# MotionBoard.net
KiCad netlist of a schematic drawn in Altium Designer
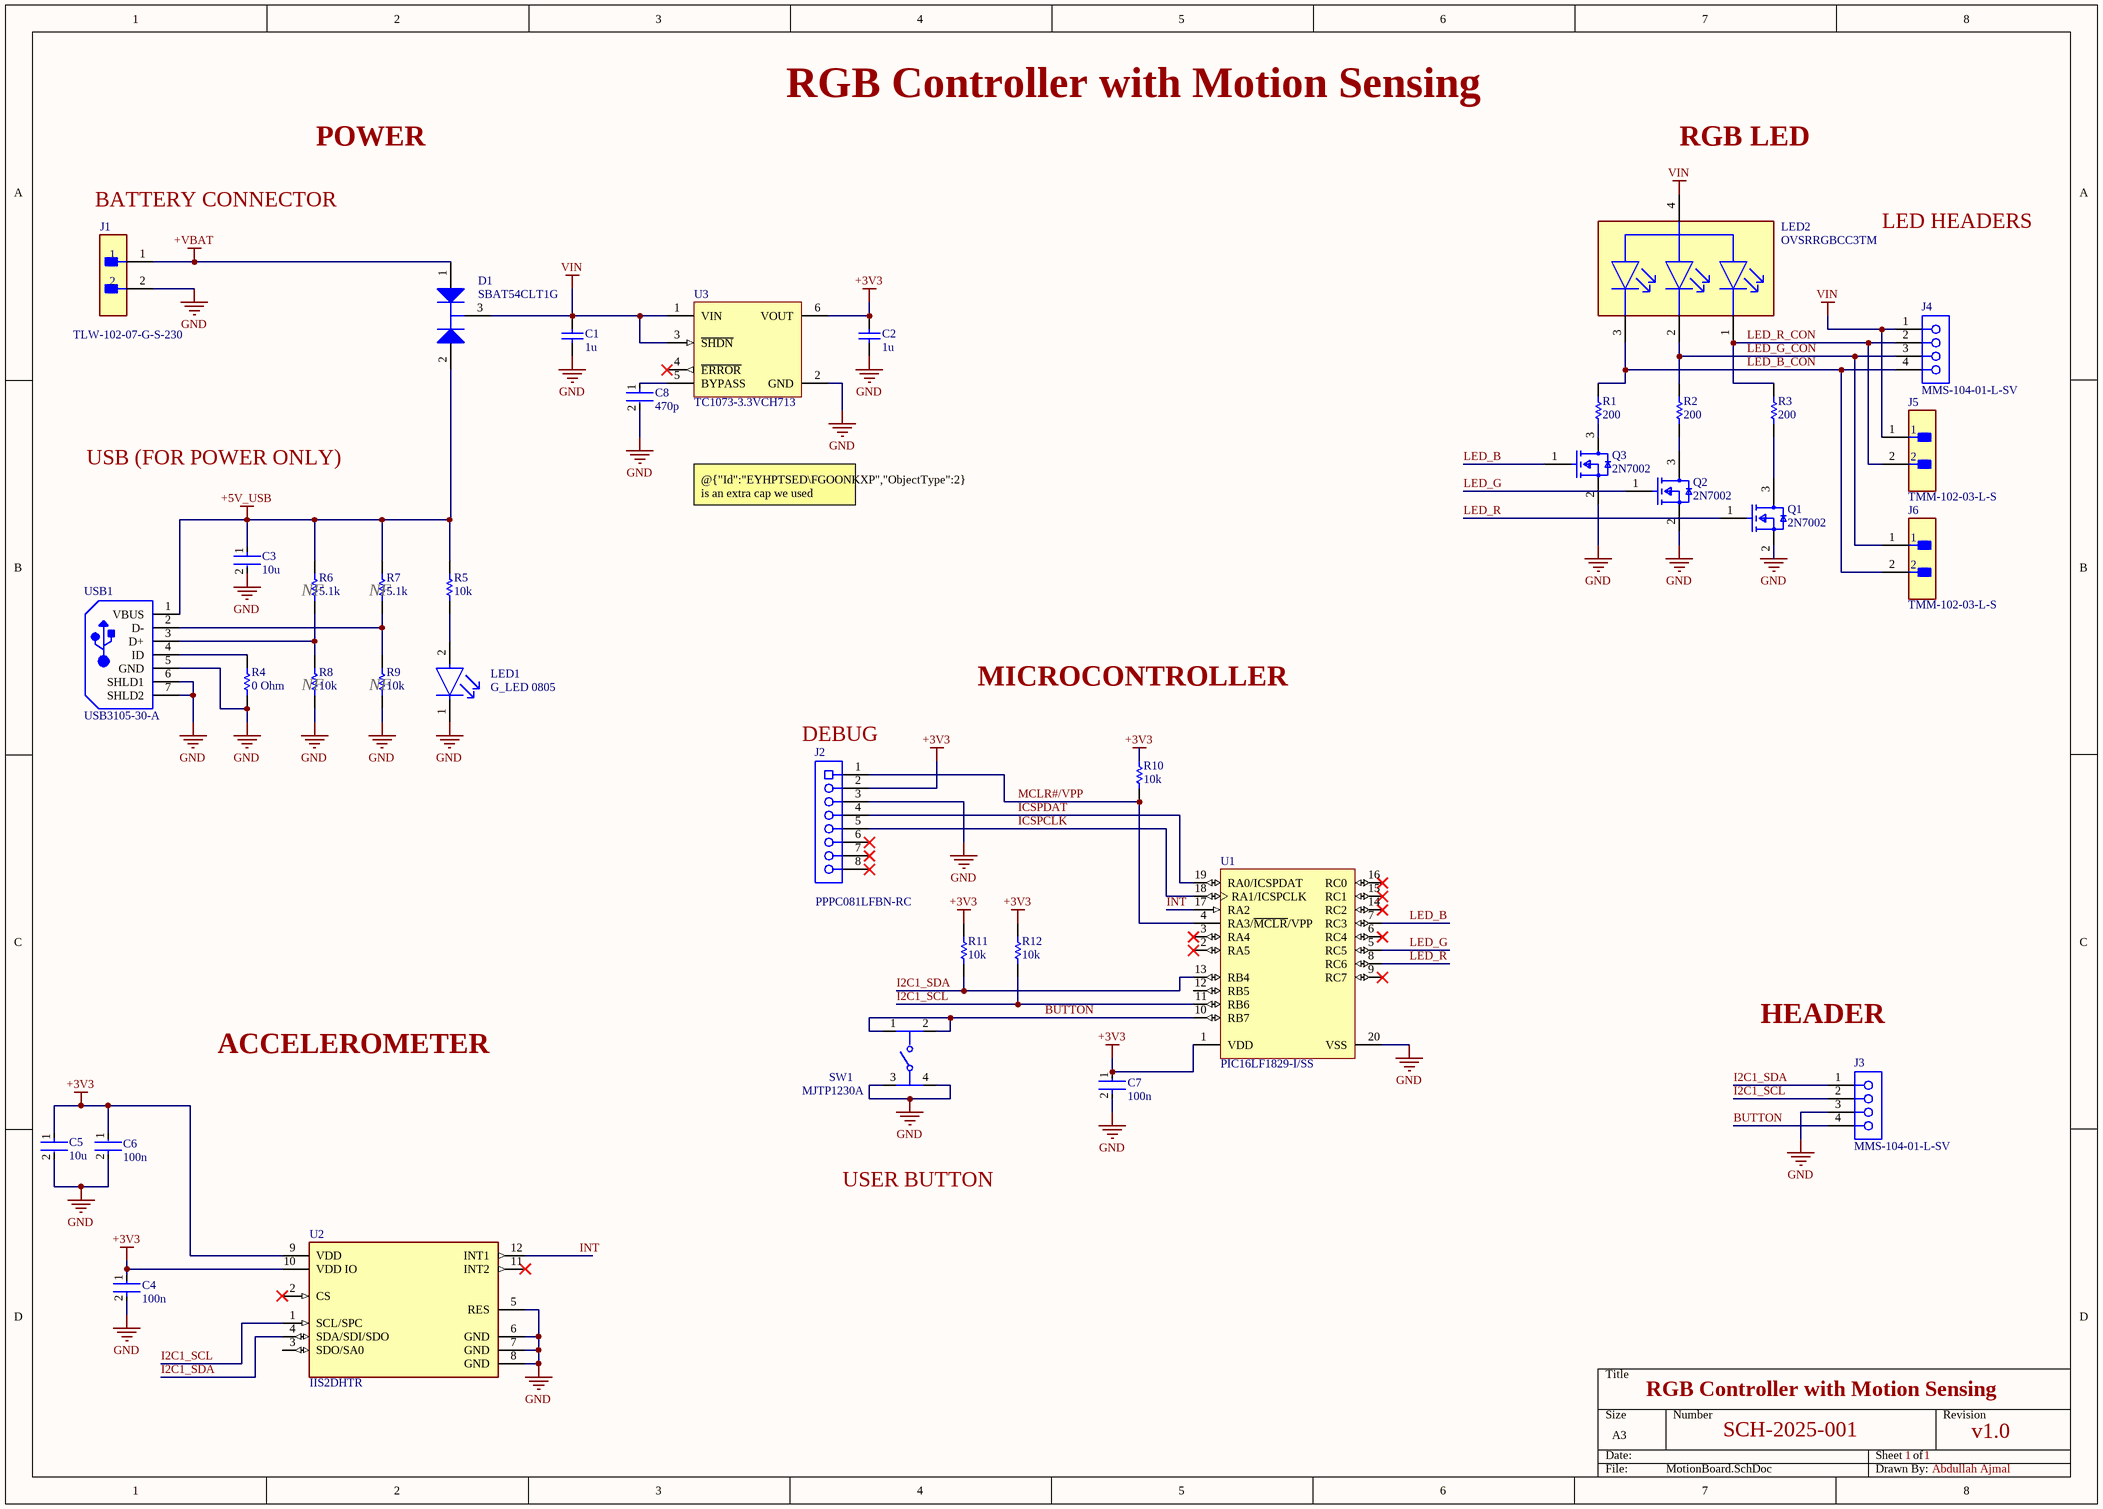
[diagram p0: MotionBoard.SchDoc]

(export (version "E")
  (design (tool "Eeschema 10.0.6"))
  (components
    (comp (ref "C1")
      (value "1u")
      (footprint "CAPC2013X140X50NL20T25")
      (fields (field (name "PART NUMBER") "C0805C105M4PACTU") (field (name "MANUFACTURER") "Kemet"))
      (libsource (lib "Altium Content Vault") (part "CAP"))
    )
    (comp (ref "C2")
      (value "1u")
      (footprint "CAPC2013X140X50NL20T25")
      (fields (field (name "PART NUMBER") "C0805C105M4PACTU") (field (name "MANUFACTURER") "Kemet"))
      (libsource (lib "Altium Content Vault") (part "CAP"))
    )
    (comp (ref "C3")
      (value "10u")
      (footprint "FP-GRM188-0_2-MFG")
      (fields (field (name "TOLERANCE") "20%"))
      (libsource (lib "Altium Content Vault") (part "11868f565c42a9108669ba33697ecf6"))
    )
    (comp (ref "C4")
      (value "100n")
      (footprint "FP-AC1210-0_85-MFG")
      (description "CAP CER 0.1UF 100V X7R 1210\r\nAC1210KKX7R0BB104")
      (fields
        (field (name "MANUFACTURER") "Yageo")
        (field (name "MANUFACTURER PART NUMBER") "AC1210KKX7R0BB104")
      )
      (libsource (lib "Altium Content Vault") (part "236180d848d6139a670b325ea6854c9"))
    )
    (comp (ref "C5")
      (value "10u")
      (footprint "FP-GRM188-0_2-MFG")
      (fields (field (name "TOLERANCE") "20%"))
      (libsource (lib "Altium Content Vault") (part "11868f565c42a9108669ba33697ecf6"))
    )
    (comp (ref "C6")
      (value "100n")
      (footprint "FP-AC1210-0_85-MFG")
      (description "CAP CER 0.1UF 100V X7R 1210\r\nAC1210KKX7R0BB104")
      (fields
        (field (name "MANUFACTURER") "Yageo")
        (field (name "MANUFACTURER PART NUMBER") "AC1210KKX7R0BB104")
      )
      (libsource (lib "Altium Content Vault") (part "236180d848d6139a670b325ea6854c9"))
    )
    (comp (ref "C7")
      (value "100n")
      (footprint "FP-AC1210-0_85-MFG")
      (description "CAP CER 0.1UF 100V X7R 1210\r\nAC1210KKX7R0BB104")
      (fields
        (field (name "MANUFACTURER") "Yageo")
        (field (name "MANUFACTURER PART NUMBER") "AC1210KKX7R0BB104")
      )
      (libsource (lib "Altium Content Vault") (part "236180d848d6139a670b325ea6854c9"))
    )
    (comp (ref "C8")
      (value "470p")
      (footprint "FP-C0402-BB-MFG")
      (description "C0402 470 pF C0G 10.00% 16 V")
      (fields (field (name "TOLERANCE") "0.1") (field (name "MANUFACTURER") "Kemet"))
      (libsource (lib "Altium Content Vault") (part "b4654b650e69147ec39a6b967a45e02"))
    )
    (comp (ref "D1")
      (value "SBAT54CLT1G")
      (footprint "ONSC-SOT-23-3-318-08_V")
      (description "Dual Common Cathode Schottky Barrier Diodes, 3-Pin SOT-23, Pb-Free, Tape and Reel")
      (fields (field (name "MANUFACTURER") "On Semiconductor"))
      (libsource (lib "Altium Content Vault") (part "ONSC-D-A1A2K3-3"))
    )
    (comp (ref "J1")
      (value "TLW-102-07-G-S-230")
      (footprint "FP-MTLW-102-07-G-S-230-MFG")
      (description "CONN HEADER VERT 2POS 2.54\r\nMMMTLW-102-07-G-S-230")
      (libsource (lib "") (part "3bc925449376181038e59eaffc5286c_1"))
    )
    (comp (ref "J2")
      (value "PPPC081LFBN-RC")
      (footprint "SLIN-PPPC081LFBN-RC_V")
      (fields (field (name "MANUFACTURER") "Sullins"))
      (libsource (lib "WePCB Projects") (part "CN-1P-F-R8"))
    )
    (comp (ref "J3")
      (value "MMS-104-01-L-SV")
      (footprint "SMTC-MMS-104-01-X-SV")
      (fields (field (name "MANUFACTURER") "Samtec"))
      (libsource (lib "Altium Content Vault") (part "SMTC-MMS-104-01-X-SV"))
    )
    (comp (ref "J4")
      (value "MMS-104-01-L-SV")
      (footprint "SMTC-MMS-104-01-X-SV")
      (fields (field (name "MANUFACTURER") "Samtec"))
      (libsource (lib "Altium Content Vault") (part "SMTC-MMS-104-01-X-SV"))
    )
    (comp (ref "J5")
      (value "TMM-102-03-L-S")
      (footprint "FP-TMM-102-03-L-S-MFG")
      (description "CONN HEADER 2POS SNGL 2MM T/H")
      (libsource (lib "Altium Content Vault") (part "3bc925449376181038e59eaffc5286c"))
    )
    (comp (ref "J6")
      (value "TMM-102-03-L-S")
      (footprint "FP-TMM-102-03-L-S-MFG")
      (description "CONN HEADER 2POS SNGL 2MM T/H")
      (libsource (lib "Altium Content Vault") (part "3bc925449376181038e59eaffc5286c"))
    )
    (comp (ref "LED1")
      (value "G_LED 0805")
      (footprint "FP-LG_R971-MFG")
      (description "LED GREEN DIFFUSED 0805 SMD\r\nQ62702P5179")
      (libsource (lib "Altium Content Vault") (part "8706943c75ba83719d021d2fdc84c58"))
    )
    (comp (ref "LED2")
      (value "OVSRRGBCC3TM")
      (footprint "FP-OVSRRGBCC3TM-MFG")
      (description "LED RGB DIFFUSED 1204 SMD")
      (libsource (lib "Altium Content Vault") (part "7312c80c6f37ed131185a1f71a63ae3"))
    )
    (comp (ref "Q1")
      (value "2N7002")
      (footprint "FP-PG-SOT23-3-MFG")
      (description "MOSFET N-CH 60V 0.3A SOT23\r\n2N7002H6327XTSA2")
      (libsource (lib "Altium Content Vault") (part "2d979dc9c009d20783d0745ce0ba7b4"))
    )
    (comp (ref "Q2")
      (value "2N7002")
      (footprint "FP-PG-SOT23-3-MFG")
      (description "MOSFET N-CH 60V 0.3A SOT23\r\n2N7002H6327XTSA2")
      (libsource (lib "Altium Content Vault") (part "2d979dc9c009d20783d0745ce0ba7b4"))
    )
    (comp (ref "Q3")
      (value "2N7002")
      (footprint "FP-PG-SOT23-3-MFG")
      (description "MOSFET N-CH 60V 0.3A SOT23\r\n2N7002H6327XTSA2")
      (libsource (lib "Altium Content Vault") (part "2d979dc9c009d20783d0745ce0ba7b4"))
    )
    (comp (ref "R1")
      (value "200")
      (footprint "RESC3225X60X45ML20T20")
      (description "CRCW1210200RJNTA")
      (fields (field (name "MANUFACTURER") "Vishay Dale"))
      (libsource (lib "Altium Content Vault") (part "RES"))
    )
    (comp (ref "R2")
      (value "200")
      (footprint "RESC3225X60X45ML20T20")
      (description "CRCW1210200RJNTA")
      (fields (field (name "MANUFACTURER") "Vishay Dale"))
      (libsource (lib "Altium Content Vault") (part "RES"))
    )
    (comp (ref "R3")
      (value "200")
      (footprint "RESC3225X60X45ML20T20")
      (description "CRCW1210200RJNTA")
      (fields (field (name "MANUFACTURER") "Vishay Dale"))
      (libsource (lib "Altium Content Vault") (part "RES"))
    )
    (comp (ref "R4")
      (value "0 Ohm")
      (footprint "RESC3116X65X45LL15T20")
      (fields (field (name "MANUFACTURER") "TE Connectivity") (field (name "TOLERANCE") "0%"))
      (libsource (lib "Altium Content Vault") (part "RES-2"))
    )
    (comp (ref "R5")
      (value "10k")
      (footprint "RESC1005X40X20NL05T10")
      (description "TNPW040210K0DEED")
      (fields (field (name "MANUFACTURER") "Vishay BCcomponents"))
      (libsource (lib "Altium Content Vault") (part "RES"))
    )
    (comp (ref "R6")
      (value "5.1k")
      (footprint "RESC1005X35X20LL05T10")
      (description "CPF0402B5K1E1")
      (fields (field (name "MANUFACTURER") "TE Connectivity / AMP"))
      (libsource (lib "Altium Content Vault") (part "RES"))
    )
    (comp (ref "R7")
      (value "5.1k")
      (footprint "RESC1005X35X20LL05T10")
      (description "CPF0402B5K1E1")
      (fields (field (name "MANUFACTURER") "TE Connectivity / AMP"))
      (libsource (lib "Altium Content Vault") (part "RES"))
    )
    (comp (ref "R8")
      (value "10k")
      (footprint "RESC1005X40X20NL05T10")
      (description "TNPW040210K0DEED")
      (fields (field (name "MANUFACTURER") "Vishay BCcomponents"))
      (libsource (lib "Altium Content Vault") (part "RES"))
    )
    (comp (ref "R9")
      (value "10k")
      (footprint "RESC1005X40X20NL05T10")
      (description "TNPW040210K0DEED")
      (fields (field (name "MANUFACTURER") "Vishay BCcomponents"))
      (libsource (lib "Altium Content Vault") (part "RES"))
    )
    (comp (ref "R10")
      (value "10k")
      (footprint "RESC1005X40X20NL05T10")
      (description "TNPW040210K0DEED")
      (fields (field (name "MANUFACTURER") "Vishay BCcomponents"))
      (libsource (lib "Altium Content Vault") (part "RES"))
    )
    (comp (ref "R11")
      (value "10k")
      (footprint "RESC1005X40X20NL05T10")
      (description "TNPW040210K0DEED")
      (fields (field (name "MANUFACTURER") "Vishay BCcomponents"))
      (libsource (lib "Altium Content Vault") (part "RES"))
    )
    (comp (ref "R12")
      (value "10k")
      (footprint "RESC1005X40X20NL05T10")
      (description "TNPW040210K0DEED")
      (fields (field (name "MANUFACTURER") "Vishay BCcomponents"))
      (libsource (lib "Altium Content Vault") (part "RES"))
    )
    (comp (ref "SW1")
      (value "MJTP1230A")
      (footprint "FP-MJTP1230A-MFG")
      (description "SWITCH TACTILE SPST-NO 0.05A 12V")
      (libsource (lib "Altium Content Vault") (part "1adf0dd01260c80cf25a44bfd6b99ba"))
    )
    (comp (ref "U1")
      (value "PIC16LF1829-I/SS")
      (footprint "MCHP-SSOP-SS20_L")
      (fields (field (name "MANUFACTURER") "Microchip"))
      (libsource (lib "Altium Content Vault") (part "MCHP-PIC16F150X_182X-20"))
    )
    (comp (ref "U2")
      (value "IIS2DHTR")
      (footprint "FP-LGA-12-8365767-MFG")
      (description "ACCEL 2-16G I2C/SPI 12LGA")
      (fields
        (field (name "MANUFACTURER") "STMicroelectronics")
        (field (name "OCTOPART") "https://octopart.com/iis2dhtr-stmicroelectronics-58218805")
      )
      (libsource (lib "Altium Content Vault") (part "0aa3afda2c658fffe6312583959f072"))
    )
    (comp (ref "U3")
      (value "TC1073-3.3VCH713")
      (footprint "SOT-23-CH6_M")
      (libsource (lib "Altium Content Vault") (part "PM-LINEREG-TC1072-IL6"))
    )
    (comp (ref "USB1")
      (value "USB3105-30-A")
      (footprint "GCT-USB3105-30-A_V")
      (description "USB 2.0 A/B Receptacle, 30 V, -55 to 85 degC, 5-Pin THD, RoHS, Tape and Reel")
      (fields (field (name "MANUFACTURER") "Global Connector Technology"))
      (libsource (lib "Altium Content Vault") (part "USB-5-2SHLD"))
    )
  )
  (nets
    (net (code "1") (name "+3V3") (class "Default")
      (node (ref "C2") (pin "2") (pinfunction "2_2") (pintype "passive"))
      (node (ref "C4") (pin "1") (pinfunction "1_1") (pintype "passive"))
      (node (ref "C5") (pin "1") (pinfunction "1_1") (pintype "passive"))
      (node (ref "C6") (pin "1") (pinfunction "1_1") (pintype "passive"))
      (node (ref "C7") (pin "1") (pinfunction "1_1") (pintype "passive"))
      (node (ref "J2") (pin "2") (pinfunction "2_2") (pintype "passive"))
      (node (ref "R10") (pin "2") (pinfunction "2_2") (pintype "passive"))
      (node (ref "R11") (pin "2") (pinfunction "2_2") (pintype "passive"))
      (node (ref "R12") (pin "2") (pinfunction "2_2") (pintype "passive"))
      (node (ref "U1") (pin "1") (pinfunction "VDD_1") (pintype "power_in"))
      (node (ref "U2") (pin "10") (pinfunction "VDD_IO_10") (pintype "power_in"))
      (node (ref "U2") (pin "9") (pinfunction "VDD_9") (pintype "power_in"))
      (node (ref "U3") (pin "6") (pinfunction "VOUT_6") (pintype "power_in"))
    )
    (net (code "2") (name "+5V_USB") (class "Default")
      (node (ref "C3") (pin "1") (pinfunction "1_1") (pintype "passive"))
      (node (ref "D1") (pin "2") (pinfunction "A2_2") (pintype "passive"))
      (node (ref "R5") (pin "2") (pinfunction "2_2") (pintype "passive"))
      (node (ref "R6") (pin "2") (pinfunction "2_2") (pintype "passive"))
      (node (ref "R7") (pin "2") (pinfunction "2_2") (pintype "passive"))
      (node (ref "USB1") (pin "1") (pinfunction "VBUS_1") (pintype "passive"))
    )
    (net (code "3") (name "+VBAT") (class "Default")
      (node (ref "D1") (pin "1") (pinfunction "A1_1") (pintype "passive"))
      (node (ref "J1") (pin "1") (pinfunction "1_1") (pintype "passive"))
    )
    (net (code "4") (name "/BUTTON") (class "Default")
      (node (ref "J3") (pin "4") (pinfunction "4_4") (pintype "passive"))
      (node (ref "SW1") (pin "1") (pinfunction "1_1") (pintype "passive"))
      (node (ref "SW1") (pin "2") (pinfunction "2_2") (pintype "passive"))
      (node (ref "U1") (pin "10") (pinfunction "RB7_10") (pintype "bidirectional"))
    )
    (net (code "5") (name "/I2C1_SCL") (class "Default")
      (node (ref "J3") (pin "2") (pinfunction "2_2") (pintype "passive"))
      (node (ref "R12") (pin "1") (pinfunction "1_1") (pintype "passive"))
      (node (ref "U1") (pin "11") (pinfunction "RB6_11") (pintype "bidirectional"))
      (node (ref "U2") (pin "1") (pinfunction "SCL/SPC_1") (pintype "input"))
    )
    (net (code "6") (name "/I2C1_SDA") (class "Default")
      (node (ref "J3") (pin "1") (pinfunction "1_1") (pintype "passive"))
      (node (ref "R11") (pin "1") (pinfunction "1_1") (pintype "passive"))
      (node (ref "U1") (pin "13") (pinfunction "RB4_13") (pintype "bidirectional"))
      (node (ref "U2") (pin "4") (pinfunction "SDA/SDI/SDO_4") (pintype "bidirectional"))
    )
    (net (code "7") (name "/ICSPCLK") (class "Default")
      (node (ref "J2") (pin "5") (pinfunction "5_5") (pintype "passive"))
      (node (ref "U1") (pin "18") (pinfunction "RA1/ICSPCLK_18") (pintype "bidirectional"))
    )
    (net (code "8") (name "/ICSPDAT") (class "Default")
      (node (ref "J2") (pin "4") (pinfunction "4_4") (pintype "passive"))
      (node (ref "U1") (pin "19") (pinfunction "RA0/ICSPDAT_19") (pintype "bidirectional"))
    )
    (net (code "9") (name "/INT") (class "Default")
      (node (ref "U1") (pin "17") (pinfunction "RA2_17") (pintype "input"))
      (node (ref "U2") (pin "12") (pinfunction "INT1_12") (pintype "output"))
    )
    (net (code "10") (name "/LED_B") (class "Default")
      (node (ref "Q3") (pin "1") (pinfunction "gate_1") (pintype "passive"))
      (node (ref "U1") (pin "7") (pinfunction "RC3_7") (pintype "bidirectional"))
    )
    (net (code "11") (name "/LED_B_CON") (class "Default")
      (node (ref "J4") (pin "4") (pinfunction "4_4") (pintype "passive"))
      (node (ref "J6") (pin "2") (pinfunction "2_2") (pintype "passive"))
      (node (ref "LED2") (pin "3") (pinfunction "B_3") (pintype "passive"))
      (node (ref "R1") (pin "2") (pinfunction "2_2") (pintype "passive"))
    )
    (net (code "12") (name "/LED_G") (class "Default")
      (node (ref "Q2") (pin "1") (pinfunction "gate_1") (pintype "passive"))
      (node (ref "U1") (pin "5") (pinfunction "RC5_5") (pintype "bidirectional"))
    )
    (net (code "13") (name "/LED_G_CON") (class "Default")
      (node (ref "J4") (pin "3") (pinfunction "3_3") (pintype "passive"))
      (node (ref "J6") (pin "1") (pinfunction "1_1") (pintype "passive"))
      (node (ref "LED2") (pin "2") (pinfunction "G_2") (pintype "passive"))
      (node (ref "R2") (pin "2") (pinfunction "2_2") (pintype "passive"))
    )
    (net (code "14") (name "/LED_R") (class "Default")
      (node (ref "Q1") (pin "1") (pinfunction "gate_1") (pintype "passive"))
      (node (ref "U1") (pin "8") (pinfunction "RC6_8") (pintype "bidirectional"))
    )
    (net (code "15") (name "/LED_R_CON") (class "Default")
      (node (ref "J4") (pin "2") (pinfunction "2_2") (pintype "passive"))
      (node (ref "J5") (pin "2") (pinfunction "2_2") (pintype "passive"))
      (node (ref "LED2") (pin "1") (pinfunction "R_1") (pintype "passive"))
      (node (ref "R3") (pin "2") (pinfunction "2_2") (pintype "passive"))
    )
    (net (code "16") (name "/MCLR#{slash}VPP") (class "Default")
      (node (ref "J2") (pin "1") (pinfunction "1_1") (pintype "passive"))
      (node (ref "R10") (pin "1") (pinfunction "1_1") (pintype "passive"))
      (node (ref "U1") (pin "4") (pinfunction "RA3/~{MCLR}/VPP_4") (pintype "passive"))
    )
    (net (code "17") (name "GND") (class "Default")
      (node (ref "C1") (pin "1") (pinfunction "1_1") (pintype "passive"))
      (node (ref "C2") (pin "1") (pinfunction "1_1") (pintype "passive"))
      (node (ref "C3") (pin "2") (pinfunction "2_2") (pintype "passive"))
      (node (ref "C4") (pin "2") (pinfunction "2_2") (pintype "passive"))
      (node (ref "C5") (pin "2") (pinfunction "2_2") (pintype "passive"))
      (node (ref "C6") (pin "2") (pinfunction "2_2") (pintype "passive"))
      (node (ref "C7") (pin "2") (pinfunction "2_2") (pintype "passive"))
      (node (ref "C8") (pin "2") (pinfunction "2_2") (pintype "passive"))
      (node (ref "J1") (pin "2") (pinfunction "2_2") (pintype "passive"))
      (node (ref "J2") (pin "3") (pinfunction "3_3") (pintype "passive"))
      (node (ref "J3") (pin "3") (pinfunction "3_3") (pintype "passive"))
      (node (ref "LED1") (pin "1") (pinfunction "C_1") (pintype "passive"))
      (node (ref "Q1") (pin "2") (pinfunction "source_2") (pintype "passive"))
      (node (ref "Q2") (pin "2") (pinfunction "source_2") (pintype "passive"))
      (node (ref "Q3") (pin "2") (pinfunction "source_2") (pintype "passive"))
      (node (ref "R4") (pin "1") (pinfunction "1_1") (pintype "passive"))
      (node (ref "R8") (pin "1") (pinfunction "1_1") (pintype "passive"))
      (node (ref "R9") (pin "1") (pinfunction "1_1") (pintype "passive"))
      (node (ref "SW1") (pin "3") (pinfunction "3_3") (pintype "passive"))
      (node (ref "SW1") (pin "4") (pinfunction "4_4") (pintype "passive"))
      (node (ref "U1") (pin "20") (pinfunction "VSS_20") (pintype "power_in"))
      (node (ref "U2") (pin "5") (pinfunction "RES_5") (pintype "passive"))
      (node (ref "U2") (pin "6") (pinfunction "GND_6") (pintype "power_in"))
      (node (ref "U2") (pin "7") (pinfunction "GND_7") (pintype "power_in"))
      (node (ref "U2") (pin "8") (pinfunction "GND_8") (pintype "power_in"))
      (node (ref "U3") (pin "2") (pinfunction "GND_2") (pintype "power_in"))
      (node (ref "USB1") (pin "5") (pinfunction "GND_5") (pintype "passive"))
      (node (ref "USB1") (pin "6") (pinfunction "SHLD1_6") (pintype "passive"))
      (node (ref "USB1") (pin "7") (pinfunction "SHLD2_7") (pintype "passive"))
    )
    (net (code "18") (name "Net-(LED1-A)") (class "Default")
      (node (ref "LED1") (pin "2") (pinfunction "A_2") (pintype "passive"))
      (node (ref "R5") (pin "1") (pinfunction "1_1") (pintype "passive"))
    )
    (net (code "19") (name "Net-(Q1-drain)") (class "Default")
      (node (ref "Q1") (pin "3") (pinfunction "drain_3") (pintype "passive"))
      (node (ref "R3") (pin "1") (pinfunction "1_1") (pintype "passive"))
    )
    (net (code "20") (name "Net-(Q2-drain)") (class "Default")
      (node (ref "Q2") (pin "3") (pinfunction "drain_3") (pintype "passive"))
      (node (ref "R2") (pin "1") (pinfunction "1_1") (pintype "passive"))
    )
    (net (code "21") (name "Net-(Q3-drain)") (class "Default")
      (node (ref "Q3") (pin "3") (pinfunction "drain_3") (pintype "passive"))
      (node (ref "R1") (pin "1") (pinfunction "1_1") (pintype "passive"))
    )
    (net (code "22") (name "Net-(U3-BYPASS)") (class "Default")
      (node (ref "C8") (pin "1") (pinfunction "1_1") (pintype "passive"))
      (node (ref "U3") (pin "5") (pinfunction "BYPASS_5") (pintype "passive"))
    )
    (net (code "23") (name "Net-(USB1-D+)") (class "Default")
      (node (ref "R6") (pin "1") (pinfunction "1_1") (pintype "passive"))
      (node (ref "R8") (pin "2") (pinfunction "2_2") (pintype "passive"))
      (node (ref "USB1") (pin "3") (pinfunction "D+_3") (pintype "passive"))
    )
    (net (code "24") (name "Net-(USB1-D-)") (class "Default")
      (node (ref "R7") (pin "1") (pinfunction "1_1") (pintype "passive"))
      (node (ref "R9") (pin "2") (pinfunction "2_2") (pintype "passive"))
      (node (ref "USB1") (pin "2") (pinfunction "D-_2") (pintype "passive"))
    )
    (net (code "25") (name "Net-(USB1-ID)") (class "Default")
      (node (ref "R4") (pin "2") (pinfunction "2_2") (pintype "passive"))
      (node (ref "USB1") (pin "4") (pinfunction "ID_4") (pintype "passive"))
    )
    (net (code "26") (name "VIN") (class "Default")
      (node (ref "C1") (pin "2") (pinfunction "2_2") (pintype "passive"))
      (node (ref "D1") (pin "3") (pinfunction "K_3") (pintype "passive"))
      (node (ref "J4") (pin "1") (pinfunction "1_1") (pintype "passive"))
      (node (ref "J5") (pin "1") (pinfunction "1_1") (pintype "passive"))
      (node (ref "LED2") (pin "4") (pinfunction "ANODE_4") (pintype "passive"))
      (node (ref "U3") (pin "1") (pinfunction "VIN_1") (pintype "power_in"))
      (node (ref "U3") (pin "3") (pinfunction "~{SHDN}_3") (pintype "input"))
    )
    (net (code "27") (name "unconnected-(J2-Pad6)") (class "Default")
      (node (ref "J2") (pin "6") (pinfunction "6_6") (pintype "passive+no_connect"))
    )
    (net (code "28") (name "unconnected-(J2-Pad7)") (class "Default")
      (node (ref "J2") (pin "7") (pinfunction "7_7") (pintype "passive+no_connect"))
    )
    (net (code "29") (name "unconnected-(J2-Pad8)") (class "Default")
      (node (ref "J2") (pin "8") (pinfunction "8_8") (pintype "passive+no_connect"))
    )
    (net (code "30") (name "unconnected-(U1-RA4-Pad3)") (class "Default")
      (node (ref "U1") (pin "3") (pinfunction "RA4_3") (pintype "bidirectional+no_connect"))
    )
    (net (code "31") (name "unconnected-(U1-RA5-Pad2)") (class "Default")
      (node (ref "U1") (pin "2") (pinfunction "RA5_2") (pintype "bidirectional+no_connect"))
    )
    (net (code "32") (name "unconnected-(U1-RB5-Pad12)") (class "Default")
      (node (ref "U1") (pin "12") (pinfunction "RB5_12") (pintype "bidirectional"))
    )
    (net (code "33") (name "unconnected-(U1-RC0-Pad16)") (class "Default")
      (node (ref "U1") (pin "16") (pinfunction "RC0_16") (pintype "bidirectional+no_connect"))
    )
    (net (code "34") (name "unconnected-(U1-RC1-Pad15)") (class "Default")
      (node (ref "U1") (pin "15") (pinfunction "RC1_15") (pintype "bidirectional+no_connect"))
    )
    (net (code "35") (name "unconnected-(U1-RC2-Pad14)") (class "Default")
      (node (ref "U1") (pin "14") (pinfunction "RC2_14") (pintype "bidirectional+no_connect"))
    )
    (net (code "36") (name "unconnected-(U1-RC4-Pad6)") (class "Default")
      (node (ref "U1") (pin "6") (pinfunction "RC4_6") (pintype "bidirectional+no_connect"))
    )
    (net (code "37") (name "unconnected-(U1-RC7-Pad9)") (class "Default")
      (node (ref "U1") (pin "9") (pinfunction "RC7_9") (pintype "bidirectional+no_connect"))
    )
    (net (code "38") (name "unconnected-(U2-CS-Pad2)") (class "Default")
      (node (ref "U2") (pin "2") (pinfunction "CS_2") (pintype "input+no_connect"))
    )
    (net (code "39") (name "unconnected-(U2-INT2-Pad11)") (class "Default")
      (node (ref "U2") (pin "11") (pinfunction "INT2_11") (pintype "output+no_connect"))
    )
    (net (code "40") (name "unconnected-(U2-SDO{slash}SA0-Pad3)") (class "Default")
      (node (ref "U2") (pin "3") (pinfunction "SDO/SA0_3") (pintype "bidirectional"))
    )
    (net (code "41") (name "unconnected-(U3-~{ERROR}-Pad4)") (class "Default")
      (node (ref "U3") (pin "4") (pinfunction "~{ERROR}_4") (pintype "output+no_connect"))
    )
  )
)
